# Connectors.net
KiCad netlist of a schematic drawn in Altium Designer
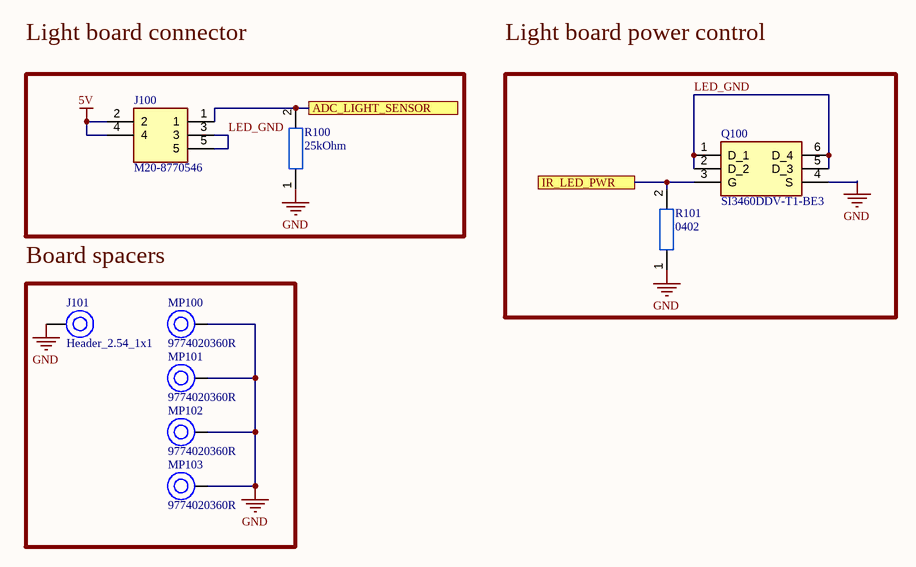
[diagram p0: Connectors.SchDoc]

(export (version "E")
  (design (tool "Eeschema 10.0.6"))
  (components
    (comp (ref "J100")
      (value "M20-8770546")
      (footprint "SamacSys:M208770546")
      (description "SMD 5 pin connector")
      (fields (field (name "MOUSER PART NUMBER") "855-M20-8770546"))
      (libsource (lib "*") (part "M20-8770546"))
    )
    (comp (ref "J101")
      (value "Header_2.54_1x1")
      (footprint "HEADER_2.54_1x1")
      (libsource (lib "Schlib1") (part "Header_2.54_1x1"))
    )
    (comp (ref "MP100")
      (value "9774020360R")
      (footprint "9774020360")
      (description "SMT STEEL SPACER, M3 INTERNAL NO")
      (libsource (lib "Altium Content Vault") (part "Spacer"))
    )
    (comp (ref "MP101")
      (value "9774020360R")
      (footprint "9774020360")
      (description "SMT STEEL SPACER, M3 INTERNAL NO")
      (libsource (lib "Altium Content Vault") (part "Spacer"))
    )
    (comp (ref "MP102")
      (value "9774020360R")
      (footprint "9774020360")
      (description "SMT STEEL SPACER, M3 INTERNAL NO")
      (libsource (lib "Altium Content Vault") (part "Spacer"))
    )
    (comp (ref "MP103")
      (value "9774020360R")
      (footprint "9774020360")
      (description "SMT STEEL SPACER, M3 INTERNAL NO")
      (libsource (lib "Altium Content Vault") (part "Spacer"))
    )
    (comp (ref "Q100")
      (value "SI3460DDV-T1-BE3")
      (footprint "SamacSys:SOT95P284X110-6N")
      (description "MOSFET (N-Channel)")
      (fields (field (name "MOUSER PART NUMBER") "78-SI3460DDV-T1-BE3"))
      (libsource (lib "*") (part "SI3460DDV-T1-BE3"))
    )
    (comp (ref "R100")
      (value "25kOhm")
      (footprint "0402_footprint")
      (description "0402 resistor")
      (libsource (lib "Schlib1") (part "Resistor_0402"))
    )
    (comp (ref "R101")
      (value "0402")
      (footprint "0402_footprint")
      (description "0402 resistor")
      (libsource (lib "Schlib1") (part "Resistor_0402"))
    )
  )
  (nets
    (net (code "1") (name "/ADC_LIGHT_SENSOR") (class "Default")
      (node (ref "J100") (pin "1") (pinfunction "1_1") (pintype "passive"))
      (node (ref "R100") (pin "2") (pinfunction "2_2") (pintype "passive"))
    )
    (net (code "2") (name "/IR_LED_PWR") (class "Default")
      (node (ref "Q100") (pin "3") (pinfunction "G_3") (pintype "passive"))
      (node (ref "R101") (pin "2") (pinfunction "2_2") (pintype "passive"))
    )
    (net (code "3") (name "/LED_GND") (class "Default")
      (node (ref "J100") (pin "3") (pinfunction "3_3") (pintype "passive"))
      (node (ref "J100") (pin "5") (pinfunction "5_5") (pintype "passive"))
      (node (ref "Q100") (pin "1") (pinfunction "D_1_1") (pintype "passive"))
      (node (ref "Q100") (pin "2") (pinfunction "D_2_2") (pintype "passive"))
      (node (ref "Q100") (pin "5") (pinfunction "D_3_5") (pintype "passive"))
      (node (ref "Q100") (pin "6") (pinfunction "D_4_6") (pintype "passive"))
    )
    (net (code "4") (name "5V") (class "Default")
      (node (ref "J100") (pin "2") (pinfunction "2_2") (pintype "passive"))
      (node (ref "J100") (pin "4") (pinfunction "4_4") (pintype "passive"))
    )
    (net (code "5") (name "GND") (class "Default")
      (node (ref "J101") (pin "0") (pinfunction "0_0") (pintype "passive"))
      (node (ref "MP100") (pin "1") (pinfunction "1_1") (pintype "passive"))
      (node (ref "MP101") (pin "1") (pinfunction "1_1") (pintype "passive"))
      (node (ref "MP102") (pin "1") (pinfunction "1_1") (pintype "passive"))
      (node (ref "MP103") (pin "1") (pinfunction "1_1") (pintype "passive"))
      (node (ref "Q100") (pin "4") (pinfunction "S_4") (pintype "passive"))
      (node (ref "R100") (pin "1") (pinfunction "1_1") (pintype "passive"))
      (node (ref "R101") (pin "1") (pinfunction "1_1") (pintype "passive"))
    )
  )
)
